# Blower_Driver.net
KiCad netlist of a schematic drawn in Altium Designer
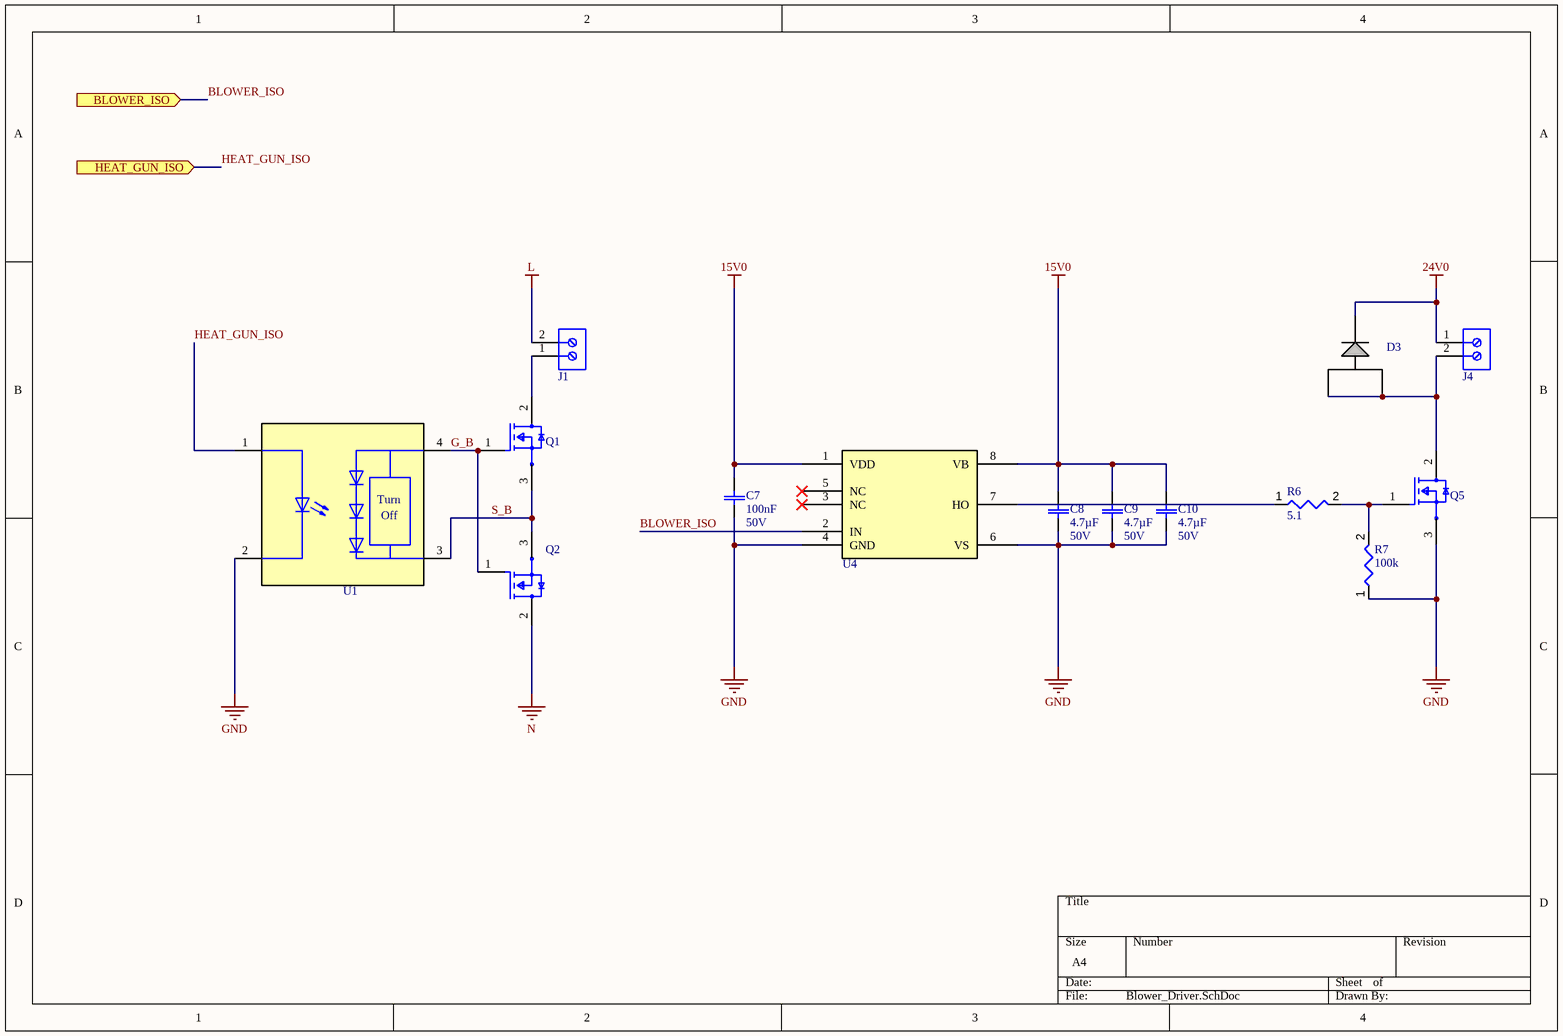
[diagram p0: Blower_Driver.SchDoc]

(export (version "E")
  (design (tool "Eeschema 10.0.6"))
  (components
    (comp (ref "C7")
      (value "100nF")
      (footprint "Generic Ceramic 0603 CAP")
      (fields
        (field (name "VOLTAGE RATING") "50V")
        (field (name "Comment") "CAP-MLCC_SMD-0603_MR-GCM_u_0.1uF_50V_10%_X8L")
      )
      (libsource (lib "Paulo Peixoto") (part "CAP_Ceramic"))
    )
    (comp (ref "C8")
      (value "4.7µF")
      (footprint "Generic Ceramic 0805 CAP")
      (fields
        (field (name "VOLTAGE RATING") "50V")
        (field (name "TOLERANCE") "10%")
        (field (name "Comment") "CAP-MLCC_SMD-0805_TDK-CGA_u_4.7uF_V_10%_X8R")
      )
      (libsource (lib "Paulo Peixoto") (part "CAP_Ceramic"))
    )
    (comp (ref "C9")
      (value "4.7µF")
      (footprint "Generic Ceramic 0805 CAP")
      (fields
        (field (name "VOLTAGE RATING") "50V")
        (field (name "TOLERANCE") "10%")
        (field (name "Comment") "CAP-MLCC_SMD-0805_TDK-CGA_u_4.7uF_V_10%_X8R")
      )
      (libsource (lib "Paulo Peixoto") (part "CAP_Ceramic"))
    )
    (comp (ref "C10")
      (value "4.7µF")
      (footprint "Generic Ceramic 0805 CAP")
      (fields
        (field (name "VOLTAGE RATING") "50V")
        (field (name "TOLERANCE") "10%")
        (field (name "Comment") "CAP-MLCC_SMD-0805_TDK-CGA_u_4.7uF_V_10%_X8R")
      )
      (libsource (lib "Paulo Peixoto") (part "CAP_Ceramic"))
    )
    (comp (ref "D3")
      (value "STPS1045B")
      (footprint "STPS1045B-Footprint-1")
      (description "Rectifier Diode, Schottky, 1 Phase, 1 Element, 10A, 45V V(RRM), Silicon, TO-252AA")
      (libsource (lib "Paulo Peixoto") (part "STPS1045B-Symbol-1"))
    )
    (comp (ref "J1")
      (value "691137710002")
      (footprint "691137710002")
      (description "2P Block Terminal")
      (libsource (lib "Paulo Peixoto") (part "Generic_2P_Block_Terminal"))
    )
    (comp (ref "J4")
      (value "691137710002")
      (footprint "691137710002")
      (description "2P Block Terminal")
      (libsource (lib "Paulo Peixoto") (part "Generic_2P_Block_Terminal"))
    )
    (comp (ref "Q1")
      (value "STD7NM50N")
      (footprint "STD7NM50N-Footprint-1")
      (description "N-channel 500V - 0.70 Ohm - 5A - TO-220 - TO-220FP - Ipak - Dpak")
      (libsource (lib "Paulo Peixoto") (part "Generic_N_FET"))
    )
    (comp (ref "Q2")
      (value "STD7NM50N")
      (footprint "STD7NM50N-Footprint-1")
      (description "N-channel 500V - 0.70 Ohm - 5A - TO-220 - TO-220FP - Ipak - Dpak")
      (libsource (lib "Paulo Peixoto") (part "Generic_N_FET"))
    )
    (comp (ref "Q5")
      (value "STD7NM50N")
      (footprint "STD7NM50N-Footprint-1")
      (description "N-channel 500V - 0.70 Ohm - 5A - TO-220 - TO-220FP - Ipak - Dpak")
      (libsource (lib "Paulo Peixoto") (part "Generic_N_FET"))
    )
    (comp (ref "R6")
      (value "5.1")
      (footprint "Generic_0805_RES")
      (fields
        (field (name "TOLERANCE") "1%")
        (field (name "POWER") "125mW")
        (field (name "Comment") "RES-TK_SMD-0805_VIS-CRCW_R_5.1R_1/10W_1%")
      )
      (libsource (lib "Paulo Peixoto") (part "Res"))
    )
    (comp (ref "R7")
      (value "100k")
      (footprint "Generic_0805_RES")
      (fields
        (field (name "POWER") "125mW")
        (field (name "TOLERANCE") "1%")
        (field (name "Comment") "RES-TK_SMD-0805_VIS-CRCW_K_100K_1/8W_1%")
      )
      (libsource (lib "Paulo Peixoto") (part "Res"))
    )
    (comp (ref "U1")
      (value "VOM1271T")
      (footprint "VOM1271T-Footprint-1")
      (description "Optocoupler DC-IN 1-CH Linear Photovoltaic DC-OUT 4-Pin SOP T/R")
      (libsource (lib "Paulo Peixoto") (part "VOM1271T-Symbol-1"))
    )
    (comp (ref "U4")
      (value "fan73711")
      (footprint "fan73711-Footprint-1")
      (description "Tape & Reel (TR) FAN73711 High-Side 2009 gate driver 25ns 125C 4A 4A 625mW")
      (libsource (lib "Paulo Peixoto") (part "fan73711-Symbol-1"))
    )
  )
  (nets
    (net (code "1") (name "/BLOWER_ISO") (class "Default")
      (node (ref "U4") (pin "2") (pinfunction "IN_2") (pintype "passive"))
    )
    (net (code "2") (name "/G_B") (class "Default")
      (node (ref "Q1") (pin "1") (pinfunction "1_1") (pintype "passive"))
      (node (ref "Q2") (pin "1") (pinfunction "1_1") (pintype "passive"))
      (node (ref "U1") (pin "4") (pinfunction "A2_4") (pintype "passive"))
    )
    (net (code "3") (name "/HEAT_GUN_ISO") (class "Default")
      (node (ref "U1") (pin "1") (pinfunction "A1_1") (pintype "passive"))
    )
    (net (code "4") (name "/S_B") (class "Default")
      (node (ref "Q1") (pin "3") (pinfunction "3_3") (pintype "passive"))
      (node (ref "Q2") (pin "3") (pinfunction "3_3") (pintype "passive"))
      (node (ref "U1") (pin "3") (pinfunction "C2_3") (pintype "passive"))
    )
    (net (code "5") (name "15V0") (class "Default")
      (node (ref "C10") (pin "2") (pinfunction "2_2") (pintype "passive"))
      (node (ref "C7") (pin "2") (pinfunction "2_2") (pintype "passive"))
      (node (ref "C8") (pin "2") (pinfunction "2_2") (pintype "passive"))
      (node (ref "C9") (pin "2") (pinfunction "2_2") (pintype "passive"))
      (node (ref "U4") (pin "1") (pinfunction "VDD_1") (pintype "power_in"))
      (node (ref "U4") (pin "8") (pinfunction "VB_8") (pintype "passive"))
    )
    (net (code "6") (name "24V0") (class "Default")
      (node (ref "D3") (pin "3") (pinfunction "2_3") (pintype "passive"))
      (node (ref "J4") (pin "1") (pinfunction "1_1") (pintype "passive"))
    )
    (net (code "7") (name "GND") (class "Default")
      (node (ref "C10") (pin "1") (pinfunction "1_1") (pintype "passive"))
      (node (ref "C7") (pin "1") (pinfunction "1_1") (pintype "passive"))
      (node (ref "C8") (pin "1") (pinfunction "1_1") (pintype "passive"))
      (node (ref "C9") (pin "1") (pinfunction "1_1") (pintype "passive"))
      (node (ref "Q5") (pin "3") (pinfunction "3_3") (pintype "passive"))
      (node (ref "R7") (pin "1") (pinfunction "1_1") (pintype "passive"))
      (node (ref "U1") (pin "2") (pinfunction "C1_2") (pintype "passive"))
      (node (ref "U4") (pin "4") (pinfunction "GND_4") (pintype "power_in"))
      (node (ref "U4") (pin "6") (pinfunction "VS_6") (pintype "passive"))
    )
    (net (code "8") (name "L") (class "Default")
      (node (ref "J1") (pin "2") (pinfunction "2_2") (pintype "passive"))
    )
    (net (code "9") (name "N") (class "Default")
      (node (ref "Q2") (pin "2") (pinfunction "2_2") (pintype "passive"))
    )
    (net (code "10") (name "Net-(D3-3)") (class "Default")
      (node (ref "D3") (pin "1") (pinfunction "1_1") (pintype "passive"))
      (node (ref "D3") (pin "2") (pinfunction "3_2") (pintype "passive"))
      (node (ref "J4") (pin "2") (pinfunction "2_2") (pintype "passive"))
      (node (ref "Q5") (pin "2") (pinfunction "2_2") (pintype "passive"))
    )
    (net (code "11") (name "Net-(J1-Pad1)") (class "Default")
      (node (ref "J1") (pin "1") (pinfunction "1_1") (pintype "passive"))
      (node (ref "Q1") (pin "2") (pinfunction "2_2") (pintype "passive"))
    )
    (net (code "12") (name "Net-(Q5-Pad1)") (class "Default")
      (node (ref "Q5") (pin "1") (pinfunction "1_1") (pintype "passive"))
      (node (ref "R6") (pin "2") (pinfunction "2_2") (pintype "passive"))
      (node (ref "R7") (pin "2") (pinfunction "2_2") (pintype "passive"))
    )
    (net (code "13") (name "Net-(U4-HO)") (class "Default")
      (node (ref "R6") (pin "1") (pinfunction "1_1") (pintype "passive"))
      (node (ref "U4") (pin "7") (pinfunction "HO_7") (pintype "passive"))
    )
    (net (code "14") (name "unconnected-(U4-NC-Pad3)") (class "Default")
      (node (ref "U4") (pin "3") (pinfunction "NC_3") (pintype "passive+no_connect"))
    )
    (net (code "15") (name "unconnected-(U4-NC-Pad5)") (class "Default")
      (node (ref "U4") (pin "5") (pinfunction "NC_5") (pintype "passive+no_connect"))
    )
  )
)
